# RS232.net
KiCad netlist of a schematic drawn in Altium Designer
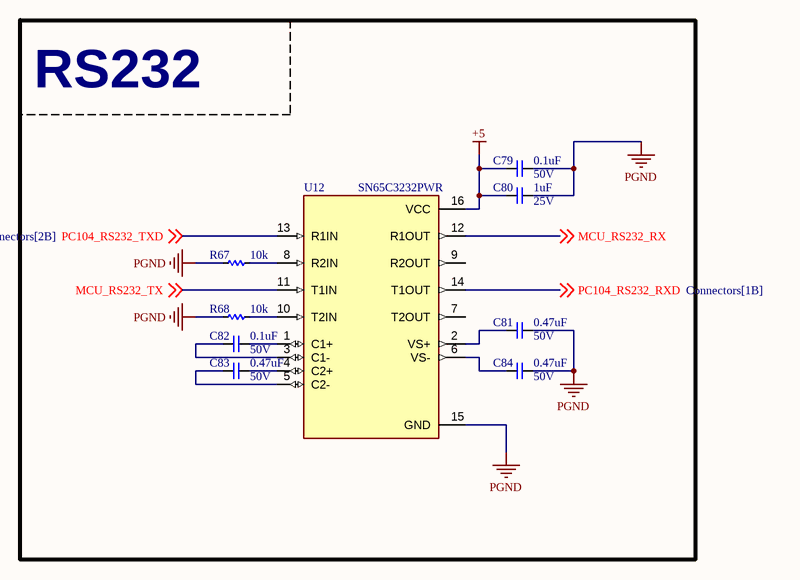
[diagram p0: RS232.SchDoc]

(export (version "E")
  (design (tool "Eeschema 10.0.6"))
  (components
    (comp (ref "C79")
      (value "0.1uF")
      (footprint "CAP_C_1608X80")
      (description "CAP")
      (fields (field (name "VOLTAGE") "50V"))
      (libsource (lib "LABLIB") (part "_CAP_C_2"))
    )
    (comp (ref "C80")
      (value "1uF")
      (footprint "CAP_C_1608X80")
      (description "CAP")
      (fields (field (name "VOLTAGE") "25V"))
      (libsource (lib "LABLIB") (part "_CAP_C_2"))
    )
    (comp (ref "C81")
      (value "0.47uF")
      (footprint "CAP_C_1608X80")
      (description "CAP")
      (fields (field (name "VOLTAGE") "50V"))
      (libsource (lib "LABLIB") (part "_CAP_C_2"))
    )
    (comp (ref "C82")
      (value "0.1uF")
      (footprint "CAP_C_1608X80")
      (description "CAP")
      (fields (field (name "VOLTAGE") "50V"))
      (libsource (lib "LABLIB") (part "_CAP_C_2"))
    )
    (comp (ref "C83")
      (value "0.47uF")
      (footprint "CAP_C_1608X80")
      (description "CAP")
      (fields (field (name "VOLTAGE") "50V"))
      (libsource (lib "LABLIB") (part "_CAP_C_2"))
    )
    (comp (ref "C84")
      (value "0.47uF")
      (footprint "CAP_C_1608X80")
      (description "CAP")
      (fields (field (name "VOLTAGE") "50V"))
      (libsource (lib "LABLIB") (part "_CAP_C_2"))
    )
    (comp (ref "R67")
      (value "10k")
      (footprint "RES_C_1608X60")
      (description "RES")
      (libsource (lib "LABLIB") (part "_RES_B_2_2"))
    )
    (comp (ref "R68")
      (value "10k")
      (footprint "RES_C_1608X60")
      (description "RES")
      (libsource (lib "LABLIB") (part "_RES_B_2_2"))
    )
    (comp (ref "U12")
      (value "SN65C3232PWR")
      (footprint "TSSOP-16")
      (libsource (lib "KIENASIY123_LIB") (part "SN65C3232PWR"))
    )
  )
  (nets
    (net (code "1") (name "+5") (class "Default")
      (node (ref "C79") (pin "2") (pinfunction "2_2") (pintype "passive"))
      (node (ref "C80") (pin "2") (pinfunction "2_2") (pintype "passive"))
      (node (ref "U12") (pin "16") (pinfunction "VCC_16") (pintype "power_in"))
    )
    (net (code "2") (name "MCU_RS232_RX") (class "Default")
      (node (ref "U12") (pin "12") (pinfunction "R1OUT_12") (pintype "output"))
    )
    (net (code "3") (name "MCU_RS232_TX") (class "Default")
      (node (ref "U12") (pin "11") (pinfunction "T1IN_11") (pintype "input"))
    )
    (net (code "4") (name "Net-(U12-C1+)") (class "Default")
      (node (ref "C82") (pin "1") (pinfunction "1_1") (pintype "passive"))
      (node (ref "U12") (pin "1") (pinfunction "C1+_1") (pintype "bidirectional"))
    )
    (net (code "5") (name "Net-(U12-C1-)") (class "Default")
      (node (ref "C82") (pin "2") (pinfunction "2_2") (pintype "passive"))
      (node (ref "U12") (pin "3") (pinfunction "C1-_3") (pintype "bidirectional"))
    )
    (net (code "6") (name "Net-(U12-C2+)") (class "Default")
      (node (ref "C83") (pin "1") (pinfunction "1_1") (pintype "passive"))
      (node (ref "U12") (pin "4") (pinfunction "C2+_4") (pintype "bidirectional"))
    )
    (net (code "7") (name "Net-(U12-C2-)") (class "Default")
      (node (ref "C83") (pin "2") (pinfunction "2_2") (pintype "passive"))
      (node (ref "U12") (pin "5") (pinfunction "C2-_5") (pintype "bidirectional"))
    )
    (net (code "8") (name "Net-(U12-R2IN)") (class "Default")
      (node (ref "R67") (pin "2") (pinfunction "2_2") (pintype "passive"))
      (node (ref "U12") (pin "8") (pinfunction "R2IN_8") (pintype "input"))
    )
    (net (code "9") (name "Net-(U12-T2IN)") (class "Default")
      (node (ref "R68") (pin "2") (pinfunction "2_2") (pintype "passive"))
      (node (ref "U12") (pin "10") (pinfunction "T2IN_10") (pintype "input"))
    )
    (net (code "10") (name "Net-(U12-VS+)") (class "Default")
      (node (ref "C81") (pin "2") (pinfunction "2_2") (pintype "passive"))
      (node (ref "U12") (pin "2") (pinfunction "VS+_2") (pintype "output"))
    )
    (net (code "11") (name "Net-(U12-VS-)") (class "Default")
      (node (ref "C84") (pin "2") (pinfunction "2_2") (pintype "passive"))
      (node (ref "U12") (pin "6") (pinfunction "VS-_6") (pintype "output"))
    )
    (net (code "12") (name "PC104_RS232_RXD") (class "Default")
      (node (ref "U12") (pin "14") (pinfunction "T1OUT_14") (pintype "output"))
    )
    (net (code "13") (name "PC104_RS232_TXD") (class "Default")
      (node (ref "U12") (pin "13") (pinfunction "R1IN_13") (pintype "input"))
    )
    (net (code "14") (name "PGND") (class "Default")
      (node (ref "C79") (pin "1") (pinfunction "1_1") (pintype "passive"))
      (node (ref "C80") (pin "1") (pinfunction "1_1") (pintype "passive"))
      (node (ref "C81") (pin "1") (pinfunction "1_1") (pintype "passive"))
      (node (ref "C84") (pin "1") (pinfunction "1_1") (pintype "passive"))
      (node (ref "R67") (pin "1") (pinfunction "1_1") (pintype "passive"))
      (node (ref "R68") (pin "1") (pinfunction "1_1") (pintype "passive"))
      (node (ref "U12") (pin "15") (pinfunction "GND_15") (pintype "power_in"))
    )
    (net (code "15") (name "unconnected-(U12-R2OUT-Pad9)") (class "Default")
      (node (ref "U12") (pin "9") (pinfunction "R2OUT_9") (pintype "output"))
    )
    (net (code "16") (name "unconnected-(U12-T2OUT-Pad7)") (class "Default")
      (node (ref "U12") (pin "7") (pinfunction "T2OUT_7") (pintype "output"))
    )
  )
)
